# Wireless_Flex_Node_SMD.net
KiCad netlist of a schematic drawn in EAGLE
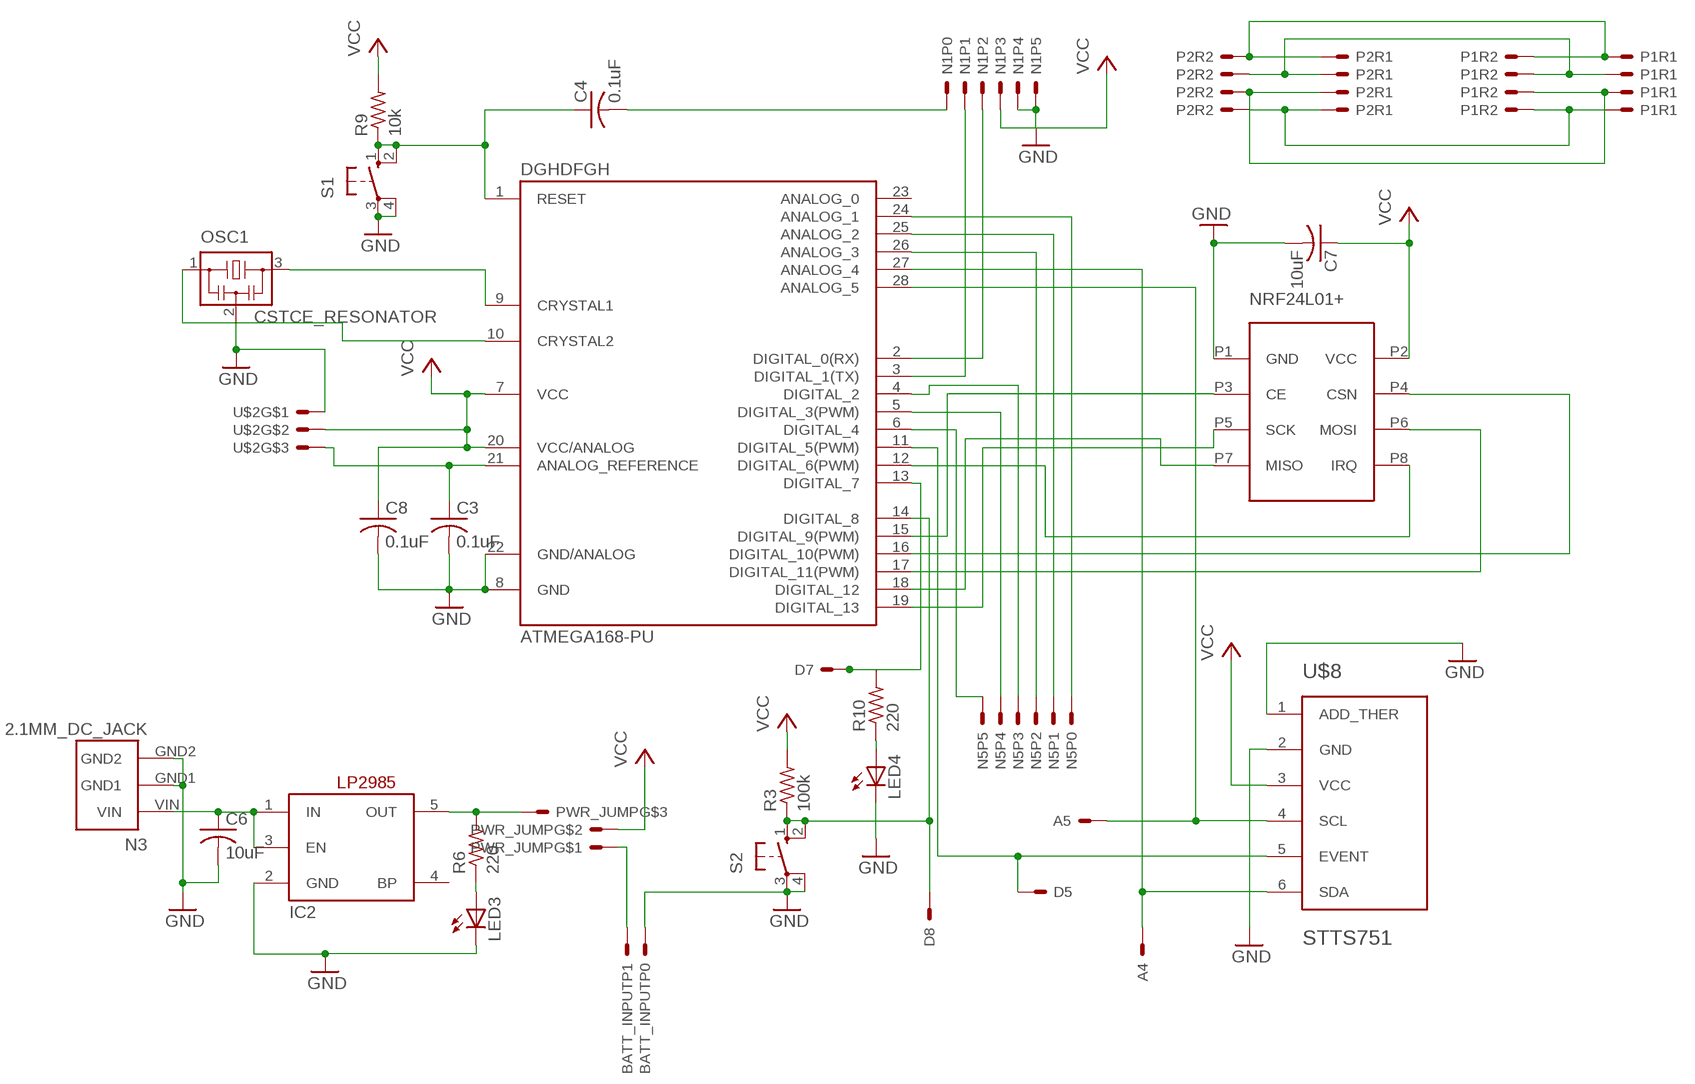
[diagram p0: schematic, sheet 1]

(export (version "E")
  (design (tool "Eeschema 10.0.6"))
  (components
    (comp (ref "A4")
      (value "1PINHEADER_S")
      (footprint "eagle-import:1PINHEADER_S")
      (libsource (lib "eagle-import") (part "1PINHEADER_S"))
    )
    (comp (ref "A5")
      (value "1PINHEADER_S")
      (footprint "eagle-import:1PINHEADER_S")
      (libsource (lib "eagle-import") (part "1PINHEADER_S"))
    )
    (comp (ref "BATT_INPUT")
      (value "2PINHEADER")
      (footprint "eagle-import:2PINHEADER")
      (libsource (lib "eagle-import") (part "2PINHEADER"))
    )
    (comp (ref "C3")
      (value "0.1uF")
      (footprint "eagle-import:C1206")
      (libsource (lib "eagle-import") (part "C-USC1206"))
    )
    (comp (ref "C4")
      (value "0.1uF")
      (footprint "eagle-import:C1206")
      (libsource (lib "eagle-import") (part "C-USC1206"))
    )
    (comp (ref "C6")
      (value "10uF")
      (footprint "eagle-import:C1206")
      (libsource (lib "eagle-import") (part "C-USC1206"))
    )
    (comp (ref "C7")
      (value "10uF")
      (footprint "eagle-import:C1206")
      (libsource (lib "eagle-import") (part "C-USC1206"))
    )
    (comp (ref "C8")
      (value "0.1uF")
      (footprint "eagle-import:C1206")
      (libsource (lib "eagle-import") (part "C-USC1206"))
    )
    (comp (ref "D5")
      (value "1PINHEADER_S")
      (footprint "eagle-import:1PINHEADER_S")
      (libsource (lib "eagle-import") (part "1PINHEADER_S"))
    )
    (comp (ref "D7")
      (value "1PINHEADER_S")
      (footprint "eagle-import:1PINHEADER_S")
      (libsource (lib "eagle-import") (part "1PINHEADER_S"))
    )
    (comp (ref "D8")
      (value "1PINHEADER_S")
      (footprint "eagle-import:1PINHEADER_S")
      (libsource (lib "eagle-import") (part "1PINHEADER_S"))
    )
    (comp (ref "DGHDFGH")
      (value "ATMEGA168-PU")
      (footprint "eagle-import:DIL28-3")
      (libsource (lib "eagle-import") (part "ATMEGA168-PU"))
    )
    (comp (ref "IC2")
      (value "LP2985")
      (footprint "eagle-import:SOT23")
      (libsource (lib "eagle-import") (part "LP2985"))
    )
    (comp (ref "LED3")
      (value "LEDSMT1206")
      (footprint "eagle-import:1206")
      (libsource (lib "eagle-import") (part "LEDSMT1206"))
    )
    (comp (ref "LED4")
      (value "LEDSMT1206")
      (footprint "eagle-import:1206")
      (libsource (lib "eagle-import") (part "LEDSMT1206"))
    )
    (comp (ref "N1")
      (value "6PINHEADER")
      (footprint "eagle-import:6PINHEADER")
      (libsource (lib "eagle-import") (part "6PINHEADER"))
    )
    (comp (ref "N3")
      (value "2.1MM_DC_JACK")
      (footprint "eagle-import:2.1MM_DC_JACK")
      (libsource (lib "eagle-import") (part "2.1MM_DC_JACK"))
    )
    (comp (ref "N5")
      (value "6PINHEADER")
      (footprint "eagle-import:6PINHEADER")
      (libsource (lib "eagle-import") (part "6PINHEADER"))
    )
    (comp (ref "NRF24L01+")
      (value "NRF24L01A")
      (footprint "eagle-import:NRF24L01")
      (libsource (lib "eagle-import") (part "NRF24L01A"))
    )
    (comp (ref "OSC1")
      (value "CSTCE_RESONATOR")
      (footprint "eagle-import:CSTCE_RESONATOR")
      (libsource (lib "eagle-import") (part "CSTCE_RESONATOR"))
    )
    (comp (ref "P1")
      (value "2X4_HEADER")
      (footprint "eagle-import:2X4_HEADER")
      (libsource (lib "eagle-import") (part "2X4_HEADER"))
    )
    (comp (ref "P2")
      (value "2X4_HEADER")
      (footprint "eagle-import:2X4_HEADER")
      (libsource (lib "eagle-import") (part "2X4_HEADER"))
    )
    (comp (ref "PWR_JUMP")
      (value "3PINHEADER")
      (footprint "eagle-import:3PINHEADER")
      (libsource (lib "eagle-import") (part "3PINHEADER"))
    )
    (comp (ref "R3")
      (value "100k")
      (footprint "eagle-import:R1206")
      (libsource (lib "eagle-import") (part "R-US_R1206"))
    )
    (comp (ref "R6")
      (value "220")
      (footprint "eagle-import:R1206")
      (libsource (lib "eagle-import") (part "R-US_R1206"))
    )
    (comp (ref "R9")
      (value "10k")
      (footprint "eagle-import:R1206")
      (libsource (lib "eagle-import") (part "R-US_R1206"))
    )
    (comp (ref "R10")
      (value "220")
      (footprint "eagle-import:R1206")
      (libsource (lib "eagle-import") (part "R-US_R1206"))
    )
    (comp (ref "S1")
      (value "10-XX")
      (footprint "eagle-import:B3F-10XX")
      (fields (field (name "MPN") "B3F-1000"))
      (libsource (lib "eagle-import") (part "10-XX"))
    )
    (comp (ref "S2")
      (value "10-XX")
      (footprint "eagle-import:B3F-10XX")
      (fields (field (name "MPN") "B3F-1000"))
      (libsource (lib "eagle-import") (part "10-XX"))
    )
    (comp (ref "U$2")
      (value "3PINHEADER")
      (footprint "eagle-import:3PINHEADER")
      (libsource (lib "eagle-import") (part "3PINHEADER"))
    )
    (comp (ref "U$8")
      (value "STTS751")
      (footprint "eagle-import:STTS751-SOT23-6L")
      (libsource (lib "eagle-import") (part "STTS751"))
    )
  )
  (nets
    (net (code "1") (name "GND") (class "Default")
      (node (ref "BATT_INPUT") (pin "P0") (pinfunction "S_P0") (pintype "passive"))
      (node (ref "C3") (pin "2") (pinfunction "2_2") (pintype "passive"))
      (node (ref "C6") (pin "2") (pinfunction "2_2") (pintype "passive"))
      (node (ref "C7") (pin "2") (pinfunction "2_2") (pintype "passive"))
      (node (ref "C8") (pin "2") (pinfunction "2_2") (pintype "passive"))
      (node (ref "DGHDFGH") (pin "22") (pinfunction "GND/ANALOG_22") (pintype "power_in"))
      (node (ref "DGHDFGH") (pin "8") (pinfunction "GND_8") (pintype "power_in"))
      (node (ref "IC2") (pin "2") (pinfunction "GND_2") (pintype "bidirectional"))
      (node (ref "LED3") (pin "C") (pinfunction "C_C") (pintype "passive"))
      (node (ref "LED4") (pin "C") (pinfunction "C_C") (pintype "passive"))
      (node (ref "N1") (pin "P4") (pinfunction "S_P4") (pintype "passive"))
      (node (ref "N1") (pin "P5") (pinfunction "S_P5") (pintype "passive"))
      (node (ref "N3") (pin "GND1") (pinfunction "GND1_GND1") (pintype "bidirectional"))
      (node (ref "N3") (pin "GND2") (pinfunction "GND2_GND2") (pintype "bidirectional"))
      (node (ref "NRF24L01+") (pin "P1") (pinfunction "GND_P1") (pintype "input"))
      (node (ref "OSC1") (pin "2") (pinfunction "2_2") (pintype "passive"))
      (node (ref "S1") (pin "3") (pinfunction "P_3") (pintype "passive"))
      (node (ref "S1") (pin "4") (pinfunction "P1_4") (pintype "passive"))
      (node (ref "S2") (pin "3") (pinfunction "P_3") (pintype "passive"))
      (node (ref "S2") (pin "4") (pinfunction "P1_4") (pintype "passive"))
      (node (ref "U$2") (pin "N0") (pinfunction "S_N0") (pintype "passive"))
      (node (ref "U$8") (pin "1") (pinfunction "ADD_THER_1") (pintype "bidirectional"))
      (node (ref "U$8") (pin "2") (pinfunction "GND_2") (pintype "bidirectional"))
    )
    (net (code "2") (name "Net-(A4-S)") (class "Default")
      (node (ref "A4") (pin "P$1") (pinfunction "S_P$1") (pintype "passive"))
      (node (ref "DGHDFGH") (pin "27") (pinfunction "ANALOG_4_27") (pintype "bidirectional"))
      (node (ref "U$8") (pin "6") (pinfunction "SDA_6") (pintype "bidirectional"))
    )
    (net (code "3") (name "Net-(A5-S)") (class "Default")
      (node (ref "A5") (pin "P$1") (pinfunction "S_P$1") (pintype "passive"))
      (node (ref "DGHDFGH") (pin "28") (pinfunction "ANALOG_5_28") (pintype "bidirectional"))
      (node (ref "U$8") (pin "4") (pinfunction "SCL_4") (pintype "bidirectional"))
    )
    (net (code "4") (name "Net-(BATT_INPUTB-S)") (class "Default")
      (node (ref "BATT_INPUT") (pin "P1") (pinfunction "S_P1") (pintype "passive"))
      (node (ref "PWR_JUMP") (pin "N0") (pinfunction "S_N0") (pintype "passive"))
    )
    (net (code "5") (name "Net-(D5-S)") (class "Default")
      (node (ref "D5") (pin "P$1") (pinfunction "S_P$1") (pintype "passive"))
      (node (ref "DGHDFGH") (pin "11") (pinfunction "DIGITAL_5(PWM)_11") (pintype "bidirectional"))
      (node (ref "U$8") (pin "5") (pinfunction "EVENT_5") (pintype "bidirectional"))
    )
    (net (code "6") (name "Net-(D7-S)") (class "Default")
      (node (ref "D7") (pin "P$1") (pinfunction "S_P$1") (pintype "passive"))
      (node (ref "DGHDFGH") (pin "13") (pinfunction "DIGITAL_7_13") (pintype "bidirectional"))
      (node (ref "R10") (pin "2") (pinfunction "2_2") (pintype "passive"))
    )
    (net (code "7") (name "Net-(D8-S)") (class "Default")
      (node (ref "D8") (pin "P$1") (pinfunction "S_P$1") (pintype "passive"))
      (node (ref "DGHDFGH") (pin "14") (pinfunction "DIGITAL_8_14") (pintype "bidirectional"))
      (node (ref "R3") (pin "1") (pinfunction "1_1") (pintype "passive"))
      (node (ref "S2") (pin "1") (pinfunction "S_1") (pintype "passive"))
      (node (ref "S2") (pin "2") (pinfunction "S1_2") (pintype "passive"))
    )
    (net (code "8") (name "Net-(DGHDFGH-ANALOG_1)") (class "Default")
      (node (ref "DGHDFGH") (pin "24") (pinfunction "ANALOG_1_24") (pintype "bidirectional"))
      (node (ref "N5") (pin "P0") (pinfunction "S_P0") (pintype "passive"))
    )
    (net (code "9") (name "Net-(DGHDFGH-ANALOG_2)") (class "Default")
      (node (ref "DGHDFGH") (pin "25") (pinfunction "ANALOG_2_25") (pintype "bidirectional"))
      (node (ref "N5") (pin "P1") (pinfunction "S_P1") (pintype "passive"))
    )
    (net (code "10") (name "Net-(DGHDFGH-ANALOG_3)") (class "Default")
      (node (ref "DGHDFGH") (pin "26") (pinfunction "ANALOG_3_26") (pintype "bidirectional"))
      (node (ref "N5") (pin "P2") (pinfunction "S_P2") (pintype "passive"))
    )
    (net (code "11") (name "Net-(DGHDFGH-ANALOG_REFERENCE)") (class "Default")
      (node (ref "C3") (pin "1") (pinfunction "1_1") (pintype "passive"))
      (node (ref "DGHDFGH") (pin "21") (pinfunction "ANALOG_REFERENCE_21") (pintype "passive"))
      (node (ref "U$2") (pin "N2") (pinfunction "S_N2") (pintype "passive"))
    )
    (net (code "12") (name "Net-(DGHDFGH-CRYSTAL1)") (class "Default")
      (node (ref "DGHDFGH") (pin "9") (pinfunction "CRYSTAL1_9") (pintype "bidirectional"))
      (node (ref "OSC1") (pin "3") (pinfunction "3_3") (pintype "passive"))
    )
    (net (code "13") (name "Net-(DGHDFGH-CRYSTAL2)") (class "Default")
      (node (ref "DGHDFGH") (pin "10") (pinfunction "CRYSTAL2_10") (pintype "bidirectional"))
      (node (ref "OSC1") (pin "1") (pinfunction "1_1") (pintype "passive"))
    )
    (net (code "14") (name "Net-(DGHDFGH-DIGITAL_0(RX))") (class "Default")
      (node (ref "DGHDFGH") (pin "2") (pinfunction "DIGITAL_0(RX)_2") (pintype "bidirectional"))
      (node (ref "N1") (pin "P2") (pinfunction "S_P2") (pintype "passive"))
    )
    (net (code "15") (name "Net-(DGHDFGH-DIGITAL_1(TX))") (class "Default")
      (node (ref "DGHDFGH") (pin "3") (pinfunction "DIGITAL_1(TX)_3") (pintype "bidirectional"))
      (node (ref "N1") (pin "P1") (pinfunction "S_P1") (pintype "passive"))
    )
    (net (code "16") (name "Net-(DGHDFGH-DIGITAL_2)") (class "Default")
      (node (ref "DGHDFGH") (pin "4") (pinfunction "DIGITAL_2_4") (pintype "bidirectional"))
      (node (ref "N5") (pin "P3") (pinfunction "S_P3") (pintype "passive"))
    )
    (net (code "17") (name "Net-(DGHDFGH-DIGITAL_3(PWM))") (class "Default")
      (node (ref "DGHDFGH") (pin "5") (pinfunction "DIGITAL_3(PWM)_5") (pintype "bidirectional"))
      (node (ref "N5") (pin "P4") (pinfunction "S_P4") (pintype "passive"))
    )
    (net (code "18") (name "Net-(DGHDFGH-DIGITAL_4)") (class "Default")
      (node (ref "DGHDFGH") (pin "6") (pinfunction "DIGITAL_4_6") (pintype "bidirectional"))
      (node (ref "N5") (pin "P5") (pinfunction "S_P5") (pintype "passive"))
    )
    (net (code "19") (name "Net-(DGHDFGH-DIGITAL_6(PWM))") (class "Default")
      (node (ref "DGHDFGH") (pin "12") (pinfunction "DIGITAL_6(PWM)_12") (pintype "bidirectional"))
      (node (ref "NRF24L01+") (pin "P8") (pinfunction "IRQ_P8") (pintype "bidirectional"))
    )
    (net (code "20") (name "Net-(DGHDFGH-DIGITAL_9(PWM))") (class "Default")
      (node (ref "DGHDFGH") (pin "15") (pinfunction "DIGITAL_9(PWM)_15") (pintype "bidirectional"))
      (node (ref "NRF24L01+") (pin "P3") (pinfunction "CE_P3") (pintype "bidirectional"))
    )
    (net (code "21") (name "Net-(DGHDFGH-DIGITAL_10(PWM))") (class "Default")
      (node (ref "DGHDFGH") (pin "16") (pinfunction "DIGITAL_10(PWM)_16") (pintype "bidirectional"))
      (node (ref "NRF24L01+") (pin "P4") (pinfunction "CSN_P4") (pintype "bidirectional"))
    )
    (net (code "22") (name "Net-(DGHDFGH-DIGITAL_11(PWM))") (class "Default")
      (node (ref "DGHDFGH") (pin "17") (pinfunction "DIGITAL_11(PWM)_17") (pintype "bidirectional"))
      (node (ref "NRF24L01+") (pin "P6") (pinfunction "MOSI_P6") (pintype "bidirectional"))
    )
    (net (code "23") (name "Net-(DGHDFGH-DIGITAL_12)") (class "Default")
      (node (ref "DGHDFGH") (pin "18") (pinfunction "DIGITAL_12_18") (pintype "bidirectional"))
      (node (ref "NRF24L01+") (pin "P7") (pinfunction "MISO_P7") (pintype "bidirectional"))
    )
    (net (code "24") (name "Net-(DGHDFGH-DIGITAL_13)") (class "Default")
      (node (ref "DGHDFGH") (pin "19") (pinfunction "DIGITAL_13_19") (pintype "bidirectional"))
      (node (ref "NRF24L01+") (pin "P5") (pinfunction "SCK_P5") (pintype "bidirectional"))
    )
    (net (code "25") (name "Net-(DGHDFGH-RESET)") (class "Default")
      (node (ref "C4") (pin "1") (pinfunction "1_1") (pintype "passive"))
      (node (ref "DGHDFGH") (pin "1") (pinfunction "RESET_1") (pintype "bidirectional"))
      (node (ref "R9") (pin "1") (pinfunction "1_1") (pintype "passive"))
      (node (ref "S1") (pin "1") (pinfunction "S_1") (pintype "passive"))
      (node (ref "S1") (pin "2") (pinfunction "S1_2") (pintype "passive"))
    )
    (net (code "26") (name "Net-(IC2-EN)") (class "Default")
      (node (ref "C6") (pin "1") (pinfunction "1_1") (pintype "passive"))
      (node (ref "IC2") (pin "1") (pinfunction "IN_1") (pintype "power_in"))
      (node (ref "IC2") (pin "3") (pinfunction "EN_3") (pintype "bidirectional"))
      (node (ref "N3") (pin "VIN") (pinfunction "VIN_VIN") (pintype "power_in"))
    )
    (net (code "27") (name "Net-(IC2-OUT)") (class "Default")
      (node (ref "IC2") (pin "5") (pinfunction "OUT_5") (pintype "power_in"))
      (node (ref "PWR_JUMP") (pin "N2") (pinfunction "S_N2") (pintype "passive"))
      (node (ref "R6") (pin "2") (pinfunction "2_2") (pintype "passive"))
    )
    (net (code "28") (name "Net-(LED3-PadA)") (class "Default")
      (node (ref "LED3") (pin "A") (pinfunction "A_A") (pintype "passive"))
      (node (ref "R6") (pin "1") (pinfunction "1_1") (pintype "passive"))
    )
    (net (code "29") (name "Net-(LED4-PadA)") (class "Default")
      (node (ref "LED4") (pin "A") (pinfunction "A_A") (pintype "passive"))
      (node (ref "R10") (pin "1") (pinfunction "1_1") (pintype "passive"))
    )
    (net (code "30") (name "Net-(N1A-S)") (class "Default")
      (node (ref "C4") (pin "2") (pinfunction "2_2") (pintype "passive"))
      (node (ref "N1") (pin "P0") (pinfunction "S_P0") (pintype "passive"))
    )
    (net (code "31") (name "Net-(P1A-S)") (class "Default")
      (node (ref "P1") (pin "P1") (pinfunction "S_P1") (pintype "passive"))
      (node (ref "P1") (pin "P5") (pinfunction "S_P5") (pintype "passive"))
      (node (ref "P2") (pin "P1") (pinfunction "S_P1") (pintype "passive"))
      (node (ref "P2") (pin "P5") (pinfunction "S_P5") (pintype "passive"))
    )
    (net (code "32") (name "Net-(P1A-S1)") (class "Default")
      (node (ref "P1") (pin "P2") (pinfunction "S1_P2") (pintype "passive"))
      (node (ref "P1") (pin "P6") (pinfunction "S1_P6") (pintype "passive"))
      (node (ref "P2") (pin "P2") (pinfunction "S1_P2") (pintype "passive"))
      (node (ref "P2") (pin "P6") (pinfunction "S1_P6") (pintype "passive"))
    )
    (net (code "33") (name "Net-(P1A-S2)") (class "Default")
      (node (ref "P1") (pin "P3") (pinfunction "S2_P3") (pintype "passive"))
      (node (ref "P1") (pin "P7") (pinfunction "S2_P7") (pintype "passive"))
      (node (ref "P2") (pin "P3") (pinfunction "S2_P3") (pintype "passive"))
      (node (ref "P2") (pin "P7") (pinfunction "S2_P7") (pintype "passive"))
    )
    (net (code "34") (name "Net-(P1A-S3)") (class "Default")
      (node (ref "P1") (pin "P4") (pinfunction "S3_P4") (pintype "passive"))
      (node (ref "P1") (pin "P8") (pinfunction "S3_P8") (pintype "passive"))
      (node (ref "P2") (pin "P4") (pinfunction "S3_P4") (pintype "passive"))
      (node (ref "P2") (pin "P8") (pinfunction "S3_P8") (pintype "passive"))
    )
    (net (code "35") (name "VCC") (class "Default")
      (node (ref "C7") (pin "1") (pinfunction "1_1") (pintype "passive"))
      (node (ref "C8") (pin "1") (pinfunction "1_1") (pintype "passive"))
      (node (ref "DGHDFGH") (pin "20") (pinfunction "VCC/ANALOG_20") (pintype "passive"))
      (node (ref "DGHDFGH") (pin "7") (pinfunction "VCC_7") (pintype "power_in"))
      (node (ref "N1") (pin "P3") (pinfunction "S_P3") (pintype "passive"))
      (node (ref "NRF24L01+") (pin "P2") (pinfunction "VCC_P2") (pintype "power_in"))
      (node (ref "PWR_JUMP") (pin "N1") (pinfunction "S_N1") (pintype "passive"))
      (node (ref "R3") (pin "2") (pinfunction "2_2") (pintype "passive"))
      (node (ref "R9") (pin "2") (pinfunction "2_2") (pintype "passive"))
      (node (ref "U$2") (pin "N1") (pinfunction "S_N1") (pintype "passive"))
      (node (ref "U$8") (pin "3") (pinfunction "VCC_3") (pintype "bidirectional"))
    )
    (net (code "36") (name "unconnected-(DGHDFGH-ANALOG_0-Pad23)") (class "Default")
      (node (ref "DGHDFGH") (pin "23") (pinfunction "ANALOG_0_23") (pintype "bidirectional"))
    )
    (net (code "37") (name "unconnected-(IC2-BP-Pad4)") (class "Default")
      (node (ref "IC2") (pin "4") (pinfunction "BP_4") (pintype "bidirectional"))
    )
  )
)
